# Sheet1.net
KiCad netlist of a schematic drawn in Altium Designer
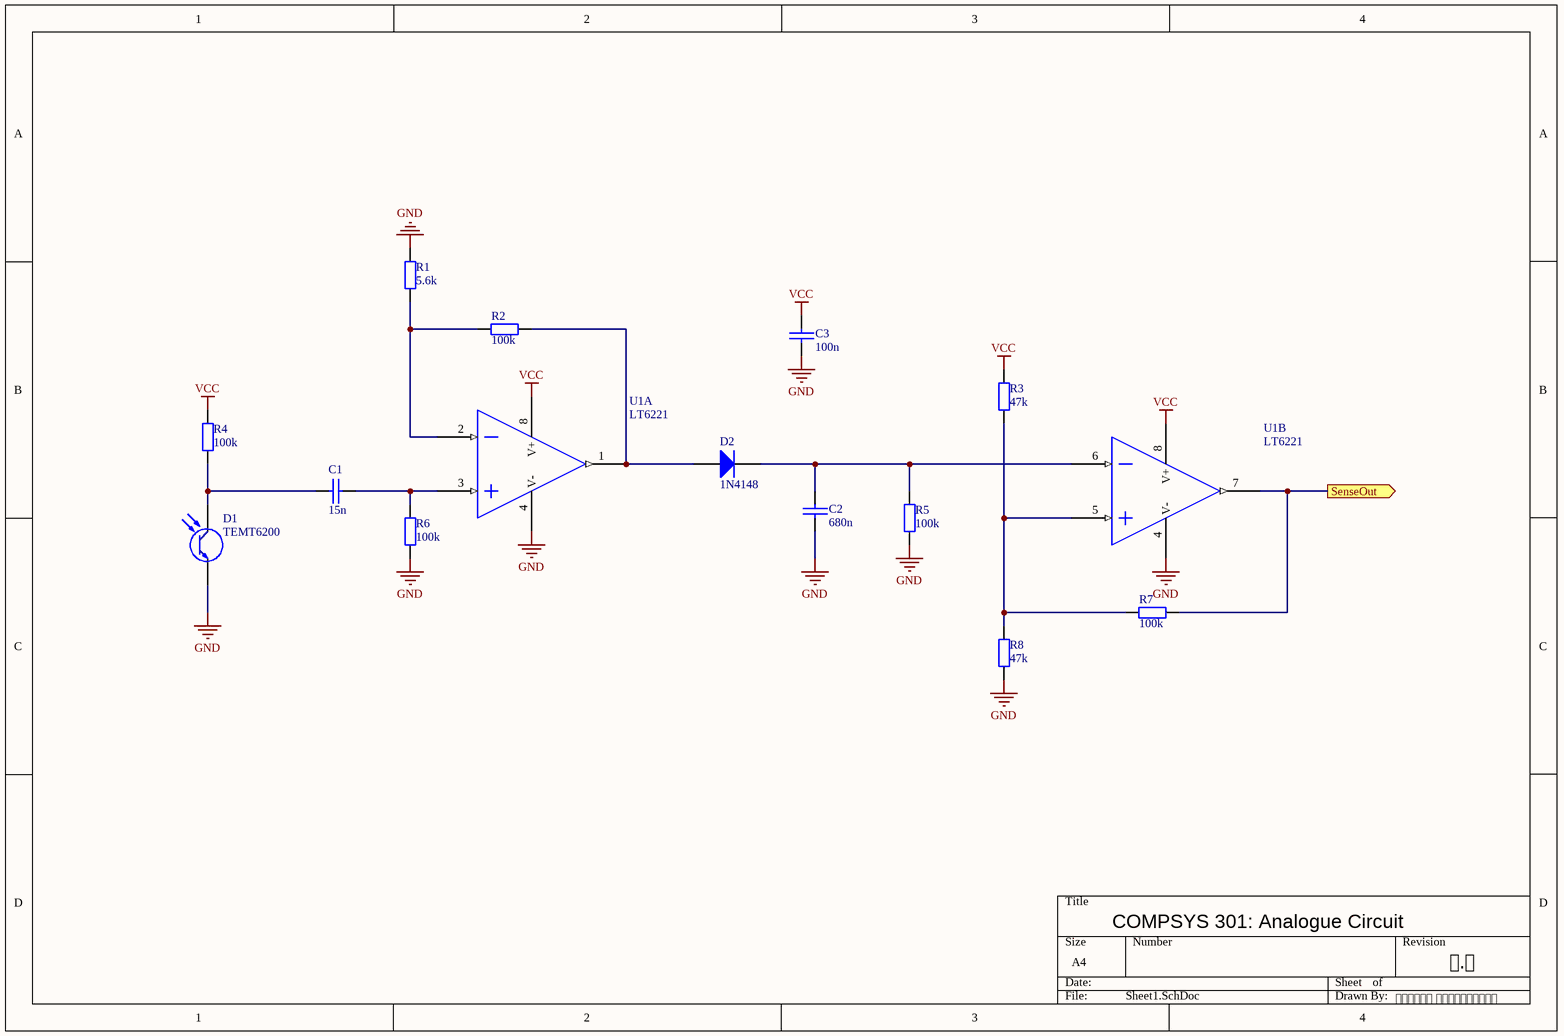
[diagram p0: Sheet1.SchDoc]

(export (version "E")
  (design (tool "Eeschema 10.0.6"))
  (components
    (comp (ref "C1")
      (value "15n")
      (footprint "ECE-CAPC1608-0603SM")
      (description "CAP CER 15nF 50V X7R SM0603")
      (libsource (lib "EceParts") (part "Cap"))
    )
    (comp (ref "C2")
      (value "680n")
      (footprint "ECE-CAPC1608-0603SM")
      (description "CAP CER 680nF 25V X7R SM0603")
      (libsource (lib "EceParts") (part "Cap"))
    )
    (comp (ref "C3")
      (value "100n")
      (footprint "ECE-CAPC1608-0603SM")
      (description "CAP CER 100nF 25V X7R SM0603")
      (libsource (lib "EceParts") (part "Cap"))
    )
    (comp (ref "D1")
      (value "TEMT6200")
      (footprint "ECE-SENSOR-0805SM")
      (description "LIGHT SENSOR TEMT6200 SM")
      (libsource (lib "EceParts") (part "TEMT6200"))
    )
    (comp (ref "D2")
      (value "1N4148")
      (footprint "ECE-DIO-SOD123SM")
      (description "DIODE GEN PURPOSE 300mA SM")
      (libsource (lib "EceParts") (part "Diode"))
    )
    (comp (ref "R1")
      (value "5.6k")
      (footprint "ECE-RESC1608-0603SM")
      (description "RES CER 5K6 1608 SM")
      (libsource (lib "") (part "Resistor_2"))
    )
    (comp (ref "R2")
      (value "100k")
      (footprint "ECE-RESC1608-0603SM")
      (description "RES CER 100K 1608 SM")
      (libsource (lib "") (part "Resistor_1"))
    )
    (comp (ref "R3")
      (value "47k")
      (footprint "ECE-RESC1608-0603SM")
      (description "RES CER 47K 1608 SM")
      (libsource (lib "") (part "Resistor_2"))
    )
    (comp (ref "R4")
      (value "100k")
      (footprint "ECE-RESC1608-0603SM")
      (description "RES CER 100K 1608 SM")
      (libsource (lib "") (part "Resistor_2"))
    )
    (comp (ref "R5")
      (value "100k")
      (footprint "ECE-RESC1608-0603SM")
      (description "RES CER 100K 1608 SM")
      (libsource (lib "") (part "Resistor_2"))
    )
    (comp (ref "R6")
      (value "100k")
      (footprint "ECE-RESC1608-0603SM")
      (description "RES CER 100K 1608 SM")
      (libsource (lib "") (part "Resistor_2"))
    )
    (comp (ref "R7")
      (value "100k")
      (footprint "ECE-RESC1608-0603SM")
      (description "RES CER 100K 1608 SM")
      (libsource (lib "EceParts") (part "Resistor"))
    )
    (comp (ref "R8")
      (value "47k")
      (footprint "ECE-RESC1608-0603SM")
      (description "RES CER 47K 1608 SM")
      (libsource (lib "") (part "Resistor_2"))
    )
    (comp (ref "U1")
      (value "LT6221")
      (footprint "ECE-SO8")
      (description "IC OPAMP LT6221 DUAL SM")
      (libsource (lib "EceParts") (part "LT6221"))
    )
  )
  (nets
    (net (code "1") (name "/SenseOut") (class "Default")
      (node (ref "R7") (pin "1") (pinfunction "1_1") (pintype "passive"))
      (node (ref "U1") (pin "7") (pinfunction "OUT2_7") (pintype "output"))
    )
    (net (code "2") (name "GND") (class "Default")
      (node (ref "C2") (pin "1") (pinfunction "1_1") (pintype "passive"))
      (node (ref "C3") (pin "2") (pinfunction "2_2") (pintype "passive"))
      (node (ref "D1") (pin "1") (pinfunction "E_1") (pintype "passive"))
      (node (ref "R1") (pin "2") (pinfunction "2_2") (pintype "passive"))
      (node (ref "R5") (pin "1") (pinfunction "1_1") (pintype "passive"))
      (node (ref "R6") (pin "1") (pinfunction "1_1") (pintype "passive"))
      (node (ref "R8") (pin "1") (pinfunction "1_1") (pintype "passive"))
      (node (ref "U1") (pin "4") (pinfunction "V-_4") (pintype "power_in"))
    )
    (net (code "3") (name "Net-(D1-C)") (class "Default")
      (node (ref "C1") (pin "2") (pinfunction "2_2") (pintype "passive"))
      (node (ref "D1") (pin "2") (pinfunction "C_2") (pintype "passive"))
      (node (ref "R4") (pin "1") (pinfunction "1_1") (pintype "passive"))
    )
    (net (code "4") (name "Net-(D2-A)") (class "Default")
      (node (ref "D2") (pin "1") (pinfunction "A_1") (pintype "passive"))
      (node (ref "R2") (pin "2") (pinfunction "2_2") (pintype "passive"))
      (node (ref "U1") (pin "1") (pinfunction "OUT1_1") (pintype "output"))
    )
    (net (code "5") (name "Net-(D2-K)") (class "Default")
      (node (ref "C2") (pin "2") (pinfunction "2_2") (pintype "passive"))
      (node (ref "D2") (pin "2") (pinfunction "K_2") (pintype "passive"))
      (node (ref "R5") (pin "2") (pinfunction "2_2") (pintype "passive"))
      (node (ref "U1") (pin "6") (pinfunction "IN2(-)_6") (pintype "input"))
    )
    (net (code "6") (name "Net-(U1A-IN1(+))") (class "Default")
      (node (ref "C1") (pin "1") (pinfunction "1_1") (pintype "passive"))
      (node (ref "R6") (pin "2") (pinfunction "2_2") (pintype "passive"))
      (node (ref "U1") (pin "3") (pinfunction "IN1(+)_3") (pintype "input"))
    )
    (net (code "7") (name "Net-(U1A-IN1(-))") (class "Default")
      (node (ref "R1") (pin "1") (pinfunction "1_1") (pintype "passive"))
      (node (ref "R2") (pin "1") (pinfunction "1_1") (pintype "passive"))
      (node (ref "U1") (pin "2") (pinfunction "IN1(-)_2") (pintype "input"))
    )
    (net (code "8") (name "Net-(U1B-IN2(+))") (class "Default")
      (node (ref "R3") (pin "1") (pinfunction "1_1") (pintype "passive"))
      (node (ref "R7") (pin "2") (pinfunction "2_2") (pintype "passive"))
      (node (ref "R8") (pin "2") (pinfunction "2_2") (pintype "passive"))
      (node (ref "U1") (pin "5") (pinfunction "IN2(+)_5") (pintype "input"))
    )
    (net (code "9") (name "VCC") (class "Default")
      (node (ref "C3") (pin "1") (pinfunction "1_1") (pintype "passive"))
      (node (ref "R3") (pin "2") (pinfunction "2_2") (pintype "passive"))
      (node (ref "R4") (pin "2") (pinfunction "2_2") (pintype "passive"))
      (node (ref "U1") (pin "8") (pinfunction "V+_8") (pintype "power_in"))
    )
  )
)
